# Audio_Memory.net
KiCad netlist of a schematic drawn in Altium Designer
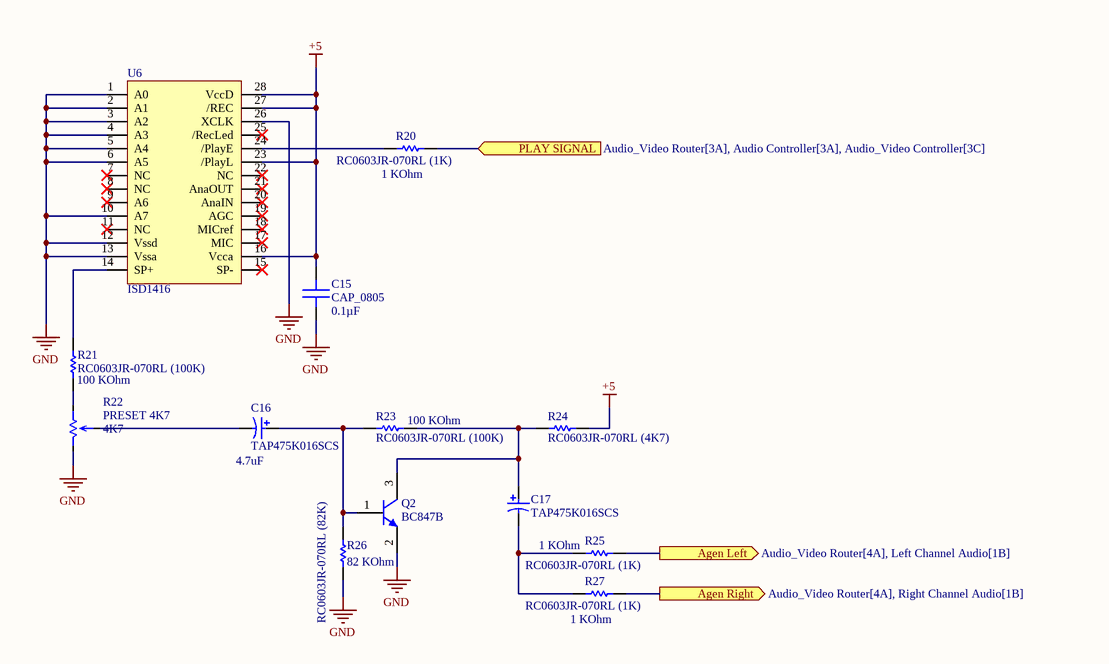
[diagram p0: Audio Memory.SchDoc]

(export (version "E")
  (design (tool "Eeschema 10.0.6"))
  (components
    (comp (ref "C15")
      (value "CAP_0805")
      (footprint "0805_CAPACITOR_DCACERES")
      (description "Capacitor SMD, encapsulado 0805")
      (fields (field (name "ALTIUM_VALUE") "0.1µF"))
      (libsource (lib "PF_Schlib") (part "CAPACITOR_0805_Caceres"))
    )
    (comp (ref "C16")
      (value "TAP475K016SCS")
      (footprint "AVX-TAP475K016SCS")
      (description "Dipped Radial Capacitor, 4.7 uF, +/- 10%, 16 V, -55 to 125 degC, RoHS, Bulk")
      (fields
        (field (name "TOLERANCE") "10%")
        (field (name "VOLTAGE") "16V")
        (field (name "CAPACITANCE") "4.7uF")
      )
      (libsource (lib "Altium Content Vault") (part "CAP-P-2"))
    )
    (comp (ref "C17")
      (value "TAP475K016SCS")
      (footprint "AVX-TAP475K016SCS")
      (description "Dipped Radial Capacitor, 4.7 uF, +/- 10%, 16 V, -55 to 125 degC, RoHS, Bulk")
      (fields (field (name "TOLERANCE") "10%") (field (name "VOLTAGE") "16V"))
      (libsource (lib "Altium Content Vault") (part "CAP-P-2"))
    )
    (comp (ref "Q2")
      (value "BC847B")
      (footprint "INF-SOT23_M")
      (description "NPN Silicon AF Transistor, 45 V VCEO, 100 mA IC, SOT23, Reel, Green")
      (fields (field (name "MANUFACTURER") "Infineon"))
      (libsource (lib "Altium Content Vault") (part "INF-BJTNPN-BEC-3"))
    )
    (comp (ref "R20")
      (value "RC0603JR-070RL (1K)")
      (footprint "RESC1608X55X25ML10T15")
      (description "Chip Resistor, 0 Ohm, +/- 5%, 0.1 W, -55 to 155 degC, 0603 (1608 Metric), RoHS, Tape and Reel")
      (fields
        (field (name "TOLERANCE") "5%")
        (field (name "RESISTANCE") "1 KOhm")
        (field (name "MANUFACTURER") "Yageo")
      )
      (libsource (lib "Altium Content Vault") (part "RES-2"))
    )
    (comp (ref "R21")
      (value "RC0603JR-070RL (100K)")
      (footprint "RESC1608X55X25ML10T15")
      (description "Chip Resistor, 0 Ohm, +/- 5%, 0.1 W, -55 to 155 degC, 0603 (1608 Metric), RoHS, Tape and Reel")
      (fields
        (field (name "TOLERANCE") "5%")
        (field (name "RESISTANCE") "100 KOhm")
        (field (name "MANUFACTURER") "Yageo")
      )
      (libsource (lib "Altium Content Vault") (part "RES-2"))
    )
    (comp (ref "R22")
      (value "PRESET 4K7")
      (footprint "3386P_PRESET_4K7_DCaceres")
      (description "Preset 4K7, Thru HoleManufacturer Part Search 3386P-1-472LF")
      (fields (field (name "ALTIUM_VALUE") "4K7") (field (name "PARTNUMBER") "3386P-1-472LF"))
      (libsource (lib "PF_Schlib") (part "Preset_4K7_Caceres"))
    )
    (comp (ref "R23")
      (value "RC0603JR-070RL (100K)")
      (footprint "RESC1608X55X25ML10T15")
      (description "Chip Resistor, 0 Ohm, +/- 5%, 0.1 W, -55 to 155 degC, 0603 (1608 Metric), RoHS, Tape and Reel")
      (fields
        (field (name "TOLERANCE") "5%")
        (field (name "RESISTANCE") "100 KOhm")
        (field (name "MANUFACTURER") "Yageo")
      )
      (libsource (lib "Altium Content Vault") (part "RES-2"))
    )
    (comp (ref "R24")
      (value "RC0603JR-070RL (4K7)")
      (footprint "RESC1608X55X25ML10T15")
      (description "Chip Resistor, 0 Ohm, +/- 5%, 0.1 W, -55 to 155 degC, 0603 (1608 Metric), RoHS, Tape and Reel")
      (fields (field (name "TOLERANCE") "5%") (field (name "MANUFACTURER") "Yageo"))
      (libsource (lib "Altium Content Vault") (part "RES-2"))
    )
    (comp (ref "R25")
      (value "RC0603JR-070RL (1K)")
      (footprint "RESC1608X55X25ML10T15")
      (description "Chip Resistor, 0 Ohm, +/- 5%, 0.1 W, -55 to 155 degC, 0603 (1608 Metric), RoHS, Tape and Reel")
      (fields
        (field (name "TOLERANCE") "5%")
        (field (name "RESISTANCE") "1 KOhm")
        (field (name "MANUFACTURER") "Yageo")
      )
      (libsource (lib "Altium Content Vault") (part "RES-2"))
    )
    (comp (ref "R26")
      (value "RC0603JR-070RL (82K)")
      (footprint "RESC1608X55X25ML10T15")
      (description "Chip Resistor, 0 Ohm, +/- 5%, 0.1 W, -55 to 155 degC, 0603 (1608 Metric), RoHS, Tape and Reel")
      (fields
        (field (name "TOLERANCE") "5%")
        (field (name "RESISTANCE") "82 KOhm")
        (field (name "MANUFACTURER") "Yageo")
      )
      (libsource (lib "Altium Content Vault") (part "RES-2"))
    )
    (comp (ref "R27")
      (value "RC0603JR-070RL (1K)")
      (footprint "RESC1608X55X25ML10T15")
      (description "Chip Resistor, 0 Ohm, +/- 5%, 0.1 W, -55 to 155 degC, 0603 (1608 Metric), RoHS, Tape and Reel")
      (fields
        (field (name "TOLERANCE") "5%")
        (field (name "RESISTANCE") "1 KOhm")
        (field (name "MANUFACTURER") "Yageo")
      )
      (libsource (lib "Altium Content Vault") (part "RES-2"))
    )
    (comp (ref "U6")
      (value "ISD1416")
      (footprint "28-Lead_0.600-Inch_PDIP_ISD1416_DCACERES")
      (fields (field (name "PARTNUMBER") "ISD1416P") (field (name "MANUFACTURER") "Nuvoton"))
      (libsource (lib "PF_Schlib") (part "ISD1416_Caceres"))
    )
  )
  (nets
    (net (code "1") (name "+5") (class "Default")
      (node (ref "C15") (pin "2") (pinfunction "2_2") (pintype "passive"))
      (node (ref "R24") (pin "2") (pinfunction "2_2") (pintype "passive"))
      (node (ref "U6") (pin "16") (pinfunction "Vcca_16") (pintype "passive"))
      (node (ref "U6") (pin "23") (pinfunction "/PlayL_23") (pintype "passive"))
      (node (ref "U6") (pin "27") (pinfunction "/REC_27") (pintype "passive"))
      (node (ref "U6") (pin "28") (pinfunction "VccD_28") (pintype "passive"))
    )
    (net (code "2") (name "/Agen Left") (class "Default")
      (node (ref "R25") (pin "1") (pinfunction "1_1") (pintype "passive"))
    )
    (net (code "3") (name "/Agen Right") (class "Default")
      (node (ref "R27") (pin "1") (pinfunction "1_1") (pintype "passive"))
    )
    (net (code "4") (name "/PLAY SIGNAL") (class "Default")
      (node (ref "R20") (pin "1") (pinfunction "1_1") (pintype "passive"))
    )
    (net (code "5") (name "GND") (class "Default")
      (node (ref "C15") (pin "1") (pinfunction "1_1") (pintype "passive"))
      (node (ref "Q2") (pin "2") (pinfunction "E_2") (pintype "passive"))
      (node (ref "R22") (pin "1") (pinfunction "1_1") (pintype "passive"))
      (node (ref "R26") (pin "2") (pinfunction "2_2") (pintype "passive"))
      (node (ref "U6") (pin "1") (pinfunction "A0_1") (pintype "passive"))
      (node (ref "U6") (pin "10") (pinfunction "A7_10") (pintype "passive"))
      (node (ref "U6") (pin "12") (pinfunction "Vssd_12") (pintype "passive"))
      (node (ref "U6") (pin "13") (pinfunction "Vssa_13") (pintype "passive"))
      (node (ref "U6") (pin "2") (pinfunction "A1_2") (pintype "passive"))
      (node (ref "U6") (pin "26") (pinfunction "XCLK_26") (pintype "passive"))
      (node (ref "U6") (pin "3") (pinfunction "A2_3") (pintype "passive"))
      (node (ref "U6") (pin "4") (pinfunction "A3_4") (pintype "passive"))
      (node (ref "U6") (pin "5") (pinfunction "A4_5") (pintype "passive"))
      (node (ref "U6") (pin "6") (pinfunction "A5_6") (pintype "passive"))
    )
    (net (code "6") (name "Net-(C16-Pad2)") (class "Default")
      (node (ref "C16") (pin "2") (pinfunction "2_2") (pintype "passive"))
      (node (ref "R22") (pin "3") (pinfunction "3_3") (pintype "passive"))
    )
    (net (code "7") (name "Net-(C17-Pad2)") (class "Default")
      (node (ref "C17") (pin "2") (pinfunction "2_2") (pintype "passive"))
      (node (ref "R25") (pin "2") (pinfunction "2_2") (pintype "passive"))
      (node (ref "R27") (pin "2") (pinfunction "2_2") (pintype "passive"))
    )
    (net (code "8") (name "Net-(Q2-B)") (class "Default")
      (node (ref "C16") (pin "1") (pinfunction "1_1") (pintype "passive"))
      (node (ref "Q2") (pin "1") (pinfunction "B_1") (pintype "passive"))
      (node (ref "R23") (pin "1") (pinfunction "1_1") (pintype "passive"))
      (node (ref "R26") (pin "1") (pinfunction "1_1") (pintype "passive"))
    )
    (net (code "9") (name "Net-(Q2-C)") (class "Default")
      (node (ref "C17") (pin "1") (pinfunction "1_1") (pintype "passive"))
      (node (ref "Q2") (pin "3") (pinfunction "C_3") (pintype "passive"))
      (node (ref "R23") (pin "2") (pinfunction "2_2") (pintype "passive"))
      (node (ref "R24") (pin "1") (pinfunction "1_1") (pintype "passive"))
    )
    (net (code "10") (name "Net-(R21-Pad2)") (class "Default")
      (node (ref "R21") (pin "2") (pinfunction "2_2") (pintype "passive"))
      (node (ref "R22") (pin "2") (pinfunction "1_2") (pintype "passive"))
    )
    (net (code "11") (name "Net-(U6-SP+)") (class "Default")
      (node (ref "R21") (pin "1") (pinfunction "1_1") (pintype "passive"))
      (node (ref "U6") (pin "14") (pinfunction "SP+_14") (pintype "passive"))
    )
    (net (code "12") (name "Net-(U6-{slash}PlayE)") (class "Default")
      (node (ref "R20") (pin "2") (pinfunction "2_2") (pintype "passive"))
      (node (ref "U6") (pin "24") (pinfunction "/PlayE_24") (pintype "passive"))
    )
    (net (code "13") (name "unconnected-(U6-A6-Pad9)") (class "Default")
      (node (ref "U6") (pin "9") (pinfunction "A6_9") (pintype "passive+no_connect"))
    )
    (net (code "14") (name "unconnected-(U6-AGC-Pad19)") (class "Default")
      (node (ref "U6") (pin "19") (pinfunction "AGC_19") (pintype "passive+no_connect"))
    )
    (net (code "15") (name "unconnected-(U6-AnaIN-Pad20)") (class "Default")
      (node (ref "U6") (pin "20") (pinfunction "AnaIN_20") (pintype "passive+no_connect"))
    )
    (net (code "16") (name "unconnected-(U6-AnaOUT-Pad21)") (class "Default")
      (node (ref "U6") (pin "21") (pinfunction "AnaOUT_21") (pintype "passive+no_connect"))
    )
    (net (code "17") (name "unconnected-(U6-MIC-Pad17)") (class "Default")
      (node (ref "U6") (pin "17") (pinfunction "MIC_17") (pintype "passive+no_connect"))
    )
    (net (code "18") (name "unconnected-(U6-MICref-Pad18)") (class "Default")
      (node (ref "U6") (pin "18") (pinfunction "MICref_18") (pintype "passive+no_connect"))
    )
    (net (code "19") (name "unconnected-(U6-NC-Pad7)") (class "Default")
      (node (ref "U6") (pin "7") (pinfunction "NC_7") (pintype "passive+no_connect"))
    )
    (net (code "20") (name "unconnected-(U6-NC-Pad8)") (class "Default")
      (node (ref "U6") (pin "8") (pinfunction "NC_8") (pintype "passive+no_connect"))
    )
    (net (code "21") (name "unconnected-(U6-NC-Pad11)") (class "Default")
      (node (ref "U6") (pin "11") (pinfunction "NC_11") (pintype "passive+no_connect"))
    )
    (net (code "22") (name "unconnected-(U6-NC-Pad22)") (class "Default")
      (node (ref "U6") (pin "22") (pinfunction "NC_22") (pintype "passive+no_connect"))
    )
    (net (code "23") (name "unconnected-(U6-SP--Pad15)") (class "Default")
      (node (ref "U6") (pin "15") (pinfunction "SP-_15") (pintype "passive+no_connect"))
    )
    (net (code "24") (name "unconnected-(U6-{slash}RecLed-Pad25)") (class "Default")
      (node (ref "U6") (pin "25") (pinfunction "/RecLed_25") (pintype "passive+no_connect"))
    )
  )
)
